# BLDC_Controller_Sch.net
KiCad netlist of a schematic drawn in Altium Designer
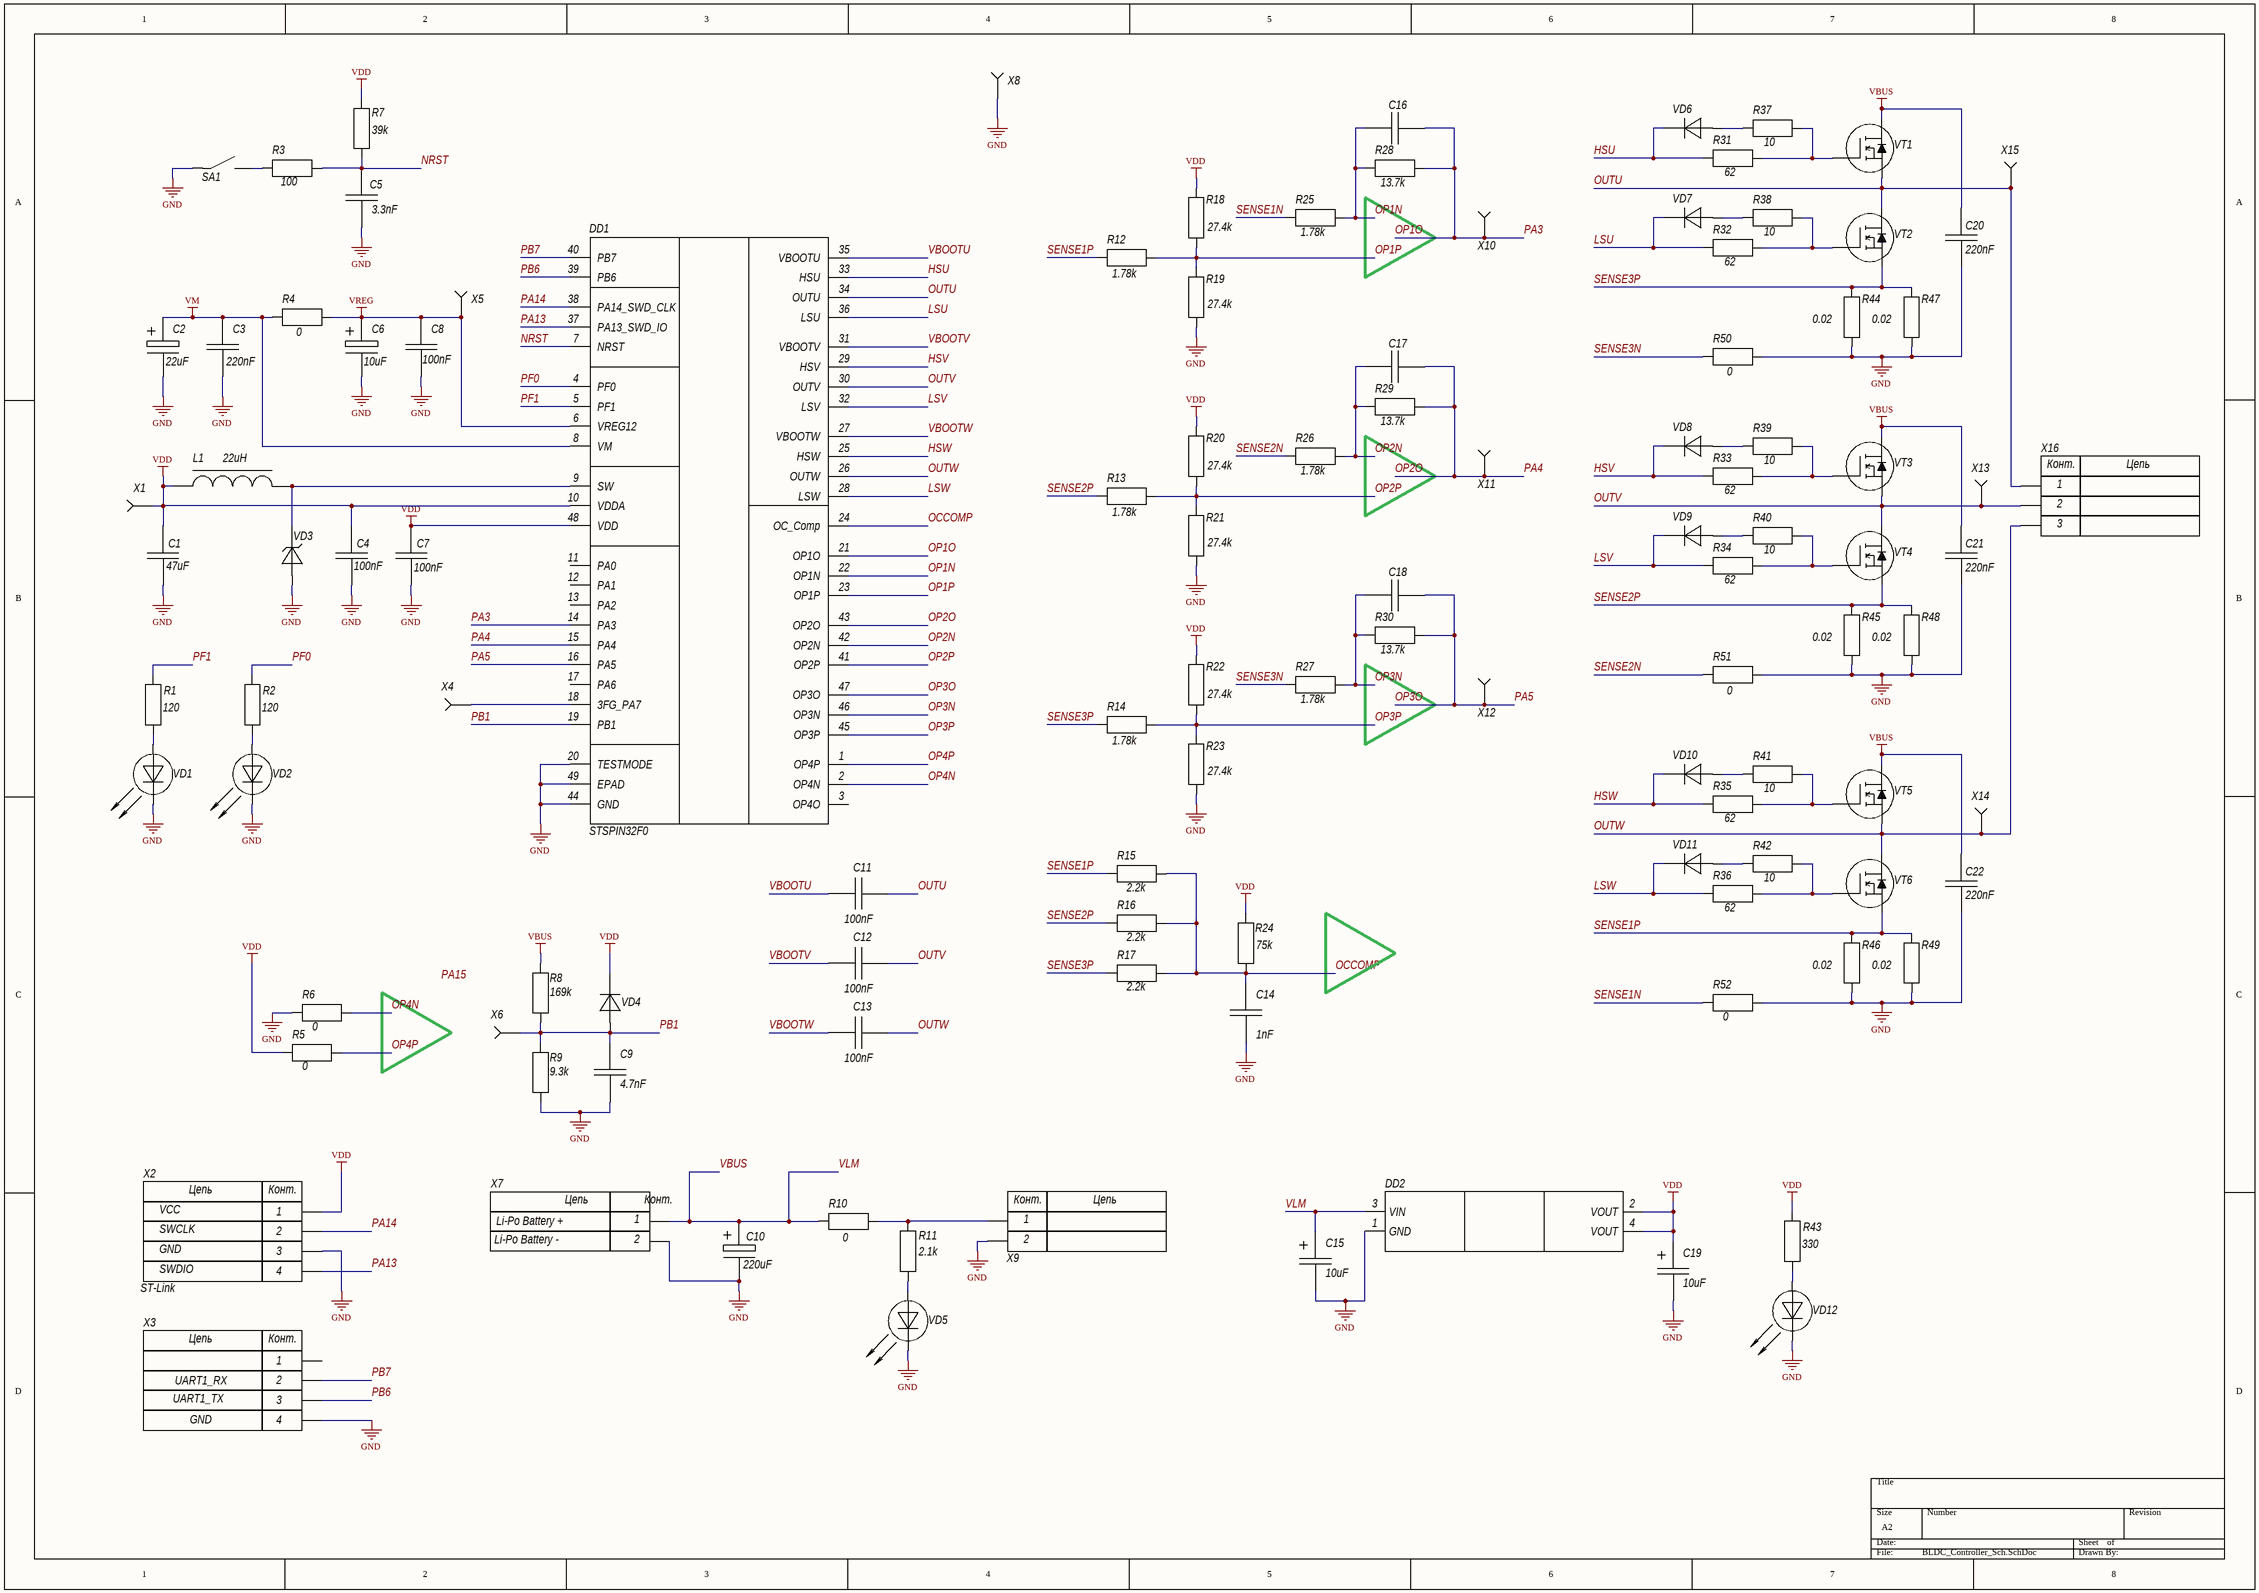
[diagram p0: BLDC_Controller_Sch.SchDoc]

(export (version "E")
  (design (tool "Eeschema 10.0.6"))
  (components
    (comp (ref "C1")
      (value "47uF")
      (footprint "CAP EIA 0603")
      (fields (field (name "Comment") "Cap EIA 0603"))
      (libsource (lib "Capacitors") (part "Cap EIA 0603"))
    )
    (comp (ref "C2")
      (value "22uF")
      (footprint "CAP EL CASE F")
      (description "8.0x10.5 mm Surface Mount Aluminum Electrolytic Capacitor")
      (fields (field (name "Comment") "Cap El SMT Case F"))
      (libsource (lib "Capacitors") (part "Cap El SMT Case F"))
    )
    (comp (ref "C3")
      (value "220nF")
      (footprint "CAP EIA 0805")
      (fields (field (name "Comment") "Cap EIA 0805"))
      (libsource (lib "Capacitors") (part "Cap EIA 0805"))
    )
    (comp (ref "C4")
      (value "100nF")
      (footprint "CAP EIA 0603")
      (fields (field (name "Comment") "Cap EIA 0603"))
      (libsource (lib "Capacitors") (part "Cap EIA 0603"))
    )
    (comp (ref "C5")
      (value "3.3nF")
      (footprint "CAP EIA 0805")
      (fields (field (name "Comment") "Cap EIA 0805"))
      (libsource (lib "Capacitors") (part "Cap EIA 0805"))
    )
    (comp (ref "C6")
      (value "10uF")
      (footprint "CAP EL CASE F")
      (description "8.0x10.5 mm Surface Mount Aluminum Electrolytic Capacitor")
      (fields (field (name "Comment") "Cap El SMT Case F"))
      (libsource (lib "Capacitors") (part "Cap El SMT Case F"))
    )
    (comp (ref "C7")
      (value "100nF")
      (footprint "CAP EIA 0603")
      (fields (field (name "Comment") "Cap EIA 0603"))
      (libsource (lib "Capacitors") (part "Cap EIA 0603"))
    )
    (comp (ref "C8")
      (value "100nF")
      (footprint "CAP EIA 0805")
      (fields (field (name "Comment") "Cap EIA 0805"))
      (libsource (lib "Capacitors") (part "Cap EIA 0805"))
    )
    (comp (ref "C9")
      (value "4.7nF")
      (footprint "CAP EIA 0603")
      (fields (field (name "Comment") "Cap EIA 0603"))
      (libsource (lib "Capacitors") (part "Cap EIA 0603"))
    )
    (comp (ref "C10")
      (value "220uF")
      (footprint "CAP EL CASE F")
      (description "8.0x10.5 mm Surface Mount Aluminum Electrolytic Capacitor")
      (fields (field (name "Comment") "Cap El SMT Case F"))
      (libsource (lib "Capacitors") (part "Cap El SMT Case F"))
    )
    (comp (ref "C11")
      (value "100nF")
      (footprint "CAP EIA 0603")
      (fields (field (name "Comment") "Cap EIA 0603"))
      (libsource (lib "Capacitors") (part "Cap EIA 0603"))
    )
    (comp (ref "C12")
      (value "100nF")
      (footprint "CAP EIA 0603")
      (fields (field (name "Comment") "Cap EIA 0603"))
      (libsource (lib "Capacitors") (part "Cap EIA 0603"))
    )
    (comp (ref "C13")
      (value "100nF")
      (footprint "CAP EIA 0603")
      (fields (field (name "Comment") "Cap EIA 0603"))
      (libsource (lib "Capacitors") (part "Cap EIA 0603"))
    )
    (comp (ref "C14")
      (value "1nF")
      (footprint "CAP EIA 0603")
      (fields (field (name "Comment") "Cap EIA 0603"))
      (libsource (lib "Capacitors") (part "Cap EIA 0603"))
    )
    (comp (ref "C15")
      (value "10uF")
      (footprint "CAP CASE A")
      (fields (field (name "Comment") "Cap El Case A (Tantalum)"))
      (libsource (lib "Capacitors") (part "Cap El Case A (Tantalum)"))
    )
    (comp (ref "C16")
      (value "Cap EIA 0603")
      (footprint "CAP EIA 0603")
      (libsource (lib "Capacitors") (part "Cap EIA 0603"))
    )
    (comp (ref "C17")
      (value "Cap EIA 0603")
      (footprint "CAP EIA 0603")
      (libsource (lib "Capacitors") (part "Cap EIA 0603"))
    )
    (comp (ref "C18")
      (value "Cap EIA 0603")
      (footprint "CAP EIA 0603")
      (libsource (lib "Capacitors") (part "Cap EIA 0603"))
    )
    (comp (ref "C19")
      (value "10uF")
      (footprint "CAP CASE A")
      (fields (field (name "Comment") "Cap El Case A (Tantalum)"))
      (libsource (lib "Capacitors") (part "Cap El Case A (Tantalum)"))
    )
    (comp (ref "C20")
      (value "220nF")
      (footprint "CAP EIA 0805")
      (fields (field (name "Comment") "Cap EIA 0805"))
      (libsource (lib "Capacitors") (part "Cap EIA 0805"))
    )
    (comp (ref "C21")
      (value "220nF")
      (footprint "CAP EIA 0805")
      (fields (field (name "Comment") "Cap EIA 0805"))
      (libsource (lib "Capacitors") (part "Cap EIA 0805"))
    )
    (comp (ref "C22")
      (value "220nF")
      (footprint "CAP EIA 0805")
      (fields (field (name "Comment") "Cap EIA 0805"))
      (libsource (lib "Capacitors") (part "Cap EIA 0805"))
    )
    (comp (ref "DD1")
      (value "STSPIN32F0")
      (footprint "VFQFPN48 7 x 7 x 1.0 - 48L")
      (description "Микросхема управления бесколлекторным эл.двигателем")
      (libsource (lib "Integrated_Circuits") (part "STSPIN32F0"))
    )
    (comp (ref "DD2")
      (value "LM1117S50")
      (footprint "SOT-223_M")
      (description "LDO Voltage Regulator")
      (fields (field (name "MANUFACTURER") "ST Microelectronics"))
      (libsource (lib "Integrated_Circuits") (part "LM1117S50"))
    )
    (comp (ref "L1")
      (value "22uH")
      (footprint "SRN3015")
      (description "Semi-shielded Power Inductors")
      (fields (field (name "MANUFACTURER") "Bourns"))
      (libsource (lib "Inductors") (part "SRN3015"))
    )
    (comp (ref "R1")
      (value "120")
      (footprint "RES EIA 0603")
      (fields (field (name "Comment") "Res EIA 0603"))
      (libsource (lib "Resistors") (part "Res EIA 0603"))
    )
    (comp (ref "R2")
      (value "120")
      (footprint "RES EIA 0603")
      (fields (field (name "Comment") "Res EIA 0603"))
      (libsource (lib "Resistors") (part "Res EIA 0603"))
    )
    (comp (ref "R3")
      (value "100")
      (footprint "RES EIA 0603")
      (fields (field (name "Comment") "Res EIA 0603"))
      (libsource (lib "Resistors") (part "Res EIA 0603"))
    )
    (comp (ref "R4")
      (value "0")
      (footprint "RES EIA 0603")
      (fields (field (name "Comment") "Res EIA 0603"))
      (libsource (lib "Resistors") (part "Res EIA 0603"))
    )
    (comp (ref "R5")
      (value "0")
      (footprint "RES EIA 0603")
      (fields (field (name "Comment") "Res EIA 0603"))
      (libsource (lib "Resistors") (part "Res EIA 0603"))
    )
    (comp (ref "R6")
      (value "0")
      (footprint "RES EIA 0603")
      (fields (field (name "Comment") "Res EIA 0603"))
      (libsource (lib "Resistors") (part "Res EIA 0603"))
    )
    (comp (ref "R7")
      (value "39k")
      (footprint "RES EIA 0603")
      (fields (field (name "Comment") "Res EIA 0603"))
      (libsource (lib "Resistors") (part "Res EIA 0603"))
    )
    (comp (ref "R8")
      (value "169k")
      (footprint "RES EIA 0603")
      (fields (field (name "Comment") "Res EIA 0603"))
      (libsource (lib "Resistors") (part "Res EIA 0603"))
    )
    (comp (ref "R9")
      (value "9.3k")
      (footprint "RES EIA 0603")
      (fields (field (name "Comment") "Res EIA 0603"))
      (libsource (lib "Resistors") (part "Res EIA 0603"))
    )
    (comp (ref "R10")
      (value "0")
      (footprint "RES EIA 0603")
      (fields (field (name "Comment") "Res EIA 0603"))
      (libsource (lib "Resistors") (part "Res EIA 0603"))
    )
    (comp (ref "R11")
      (value "2.1k")
      (footprint "RES EIA 0805")
      (fields (field (name "Comment") "Res EIA 0805"))
      (libsource (lib "Resistors") (part "Res EIA 0805"))
    )
    (comp (ref "R12")
      (value "1.78k")
      (footprint "RES EIA 0603")
      (fields (field (name "Comment") "Res EIA 0603"))
      (libsource (lib "Resistors") (part "Res EIA 0603"))
    )
    (comp (ref "R13")
      (value "1.78k")
      (footprint "RES EIA 0603")
      (fields (field (name "Comment") "Res EIA 0603"))
      (libsource (lib "Resistors") (part "Res EIA 0603"))
    )
    (comp (ref "R14")
      (value "1.78k")
      (footprint "RES EIA 0603")
      (fields (field (name "Comment") "Res EIA 0603"))
      (libsource (lib "Resistors") (part "Res EIA 0603"))
    )
    (comp (ref "R15")
      (value "2.2k")
      (footprint "RES EIA 0603")
      (fields (field (name "Comment") "Res EIA 0603"))
      (libsource (lib "Resistors") (part "Res EIA 0603"))
    )
    (comp (ref "R16")
      (value "2.2k")
      (footprint "RES EIA 0603")
      (fields (field (name "Comment") "Res EIA 0603"))
      (libsource (lib "Resistors") (part "Res EIA 0603"))
    )
    (comp (ref "R17")
      (value "2.2k")
      (footprint "RES EIA 0603")
      (fields (field (name "Comment") "Res EIA 0603"))
      (libsource (lib "Resistors") (part "Res EIA 0603"))
    )
    (comp (ref "R18")
      (value "27.4k")
      (footprint "RES EIA 0603")
      (fields (field (name "Comment") "Res EIA 0603"))
      (libsource (lib "Resistors") (part "Res EIA 0603"))
    )
    (comp (ref "R19")
      (value "27.4k")
      (footprint "RES EIA 0603")
      (fields (field (name "Comment") "Res EIA 0603"))
      (libsource (lib "Resistors") (part "Res EIA 0603"))
    )
    (comp (ref "R20")
      (value "27.4k")
      (footprint "RES EIA 0603")
      (fields (field (name "Comment") "Res EIA 0603"))
      (libsource (lib "Resistors") (part "Res EIA 0603"))
    )
    (comp (ref "R21")
      (value "27.4k")
      (footprint "RES EIA 0603")
      (fields (field (name "Comment") "Res EIA 0603"))
      (libsource (lib "Resistors") (part "Res EIA 0603"))
    )
    (comp (ref "R22")
      (value "27.4k")
      (footprint "RES EIA 0603")
      (fields (field (name "Comment") "Res EIA 0603"))
      (libsource (lib "Resistors") (part "Res EIA 0603"))
    )
    (comp (ref "R23")
      (value "27.4k")
      (footprint "RES EIA 0603")
      (fields (field (name "Comment") "Res EIA 0603"))
      (libsource (lib "Resistors") (part "Res EIA 0603"))
    )
    (comp (ref "R24")
      (value "75k")
      (footprint "RES EIA 0603")
      (fields (field (name "Comment") "Res EIA 0603"))
      (libsource (lib "Resistors") (part "Res EIA 0603"))
    )
    (comp (ref "R25")
      (value "1.78k")
      (footprint "RES EIA 0603")
      (fields (field (name "Comment") "Res EIA 0603"))
      (libsource (lib "Resistors") (part "Res EIA 0603"))
    )
    (comp (ref "R26")
      (value "1.78k")
      (footprint "RES EIA 0603")
      (fields (field (name "Comment") "Res EIA 0603"))
      (libsource (lib "Resistors") (part "Res EIA 0603"))
    )
    (comp (ref "R27")
      (value "1.78k")
      (footprint "RES EIA 0603")
      (fields (field (name "Comment") "Res EIA 0603"))
      (libsource (lib "Resistors") (part "Res EIA 0603"))
    )
    (comp (ref "R28")
      (value "13.7k")
      (footprint "RES EIA 0603")
      (fields (field (name "Comment") "Res EIA 0603"))
      (libsource (lib "Resistors") (part "Res EIA 0603"))
    )
    (comp (ref "R29")
      (value "13.7k")
      (footprint "RES EIA 0603")
      (fields (field (name "Comment") "Res EIA 0603"))
      (libsource (lib "Resistors") (part "Res EIA 0603"))
    )
    (comp (ref "R30")
      (value "13.7k")
      (footprint "RES EIA 0603")
      (fields (field (name "Comment") "Res EIA 0603"))
      (libsource (lib "Resistors") (part "Res EIA 0603"))
    )
    (comp (ref "R31")
      (value "62")
      (footprint "RES EIA 0603")
      (fields (field (name "Comment") "Res EIA 0603"))
      (libsource (lib "Resistors") (part "Res EIA 0603"))
    )
    (comp (ref "R32")
      (value "62")
      (footprint "RES EIA 0603")
      (fields (field (name "Comment") "Res EIA 0603"))
      (libsource (lib "Resistors") (part "Res EIA 0603"))
    )
    (comp (ref "R33")
      (value "62")
      (footprint "RES EIA 0603")
      (fields (field (name "Comment") "Res EIA 0603"))
      (libsource (lib "Resistors") (part "Res EIA 0603"))
    )
    (comp (ref "R34")
      (value "62")
      (footprint "RES EIA 0603")
      (fields (field (name "Comment") "Res EIA 0603"))
      (libsource (lib "Resistors") (part "Res EIA 0603"))
    )
    (comp (ref "R35")
      (value "62")
      (footprint "RES EIA 0603")
      (fields (field (name "Comment") "Res EIA 0603"))
      (libsource (lib "Resistors") (part "Res EIA 0603"))
    )
    (comp (ref "R36")
      (value "62")
      (footprint "RES EIA 0603")
      (fields (field (name "Comment") "Res EIA 0603"))
      (libsource (lib "Resistors") (part "Res EIA 0603"))
    )
    (comp (ref "R37")
      (value "10")
      (footprint "RES EIA 0603")
      (fields (field (name "Comment") "Res EIA 0603"))
      (libsource (lib "Resistors") (part "Res EIA 0603"))
    )
    (comp (ref "R38")
      (value "10")
      (footprint "RES EIA 0603")
      (fields (field (name "Comment") "Res EIA 0603"))
      (libsource (lib "Resistors") (part "Res EIA 0603"))
    )
    (comp (ref "R39")
      (value "10")
      (footprint "RES EIA 0603")
      (fields (field (name "Comment") "Res EIA 0603"))
      (libsource (lib "Resistors") (part "Res EIA 0603"))
    )
    (comp (ref "R40")
      (value "10")
      (footprint "RES EIA 0603")
      (fields (field (name "Comment") "Res EIA 0603"))
      (libsource (lib "Resistors") (part "Res EIA 0603"))
    )
    (comp (ref "R41")
      (value "10")
      (footprint "RES EIA 0603")
      (fields (field (name "Comment") "Res EIA 0603"))
      (libsource (lib "Resistors") (part "Res EIA 0603"))
    )
    (comp (ref "R42")
      (value "10")
      (footprint "RES EIA 0603")
      (fields (field (name "Comment") "Res EIA 0603"))
      (libsource (lib "Resistors") (part "Res EIA 0603"))
    )
    (comp (ref "R43")
      (value "330")
      (footprint "RES EIA 0603")
      (fields (field (name "Comment") "Res EIA 0603"))
      (libsource (lib "Resistors") (part "Res EIA 0603"))
    )
    (comp (ref "R44")
      (value "0.02")
      (footprint "RES EIA 2512")
      (fields (field (name "Comment") "Res EIA 2512"))
      (libsource (lib "Resistors") (part "Res EIA 2512"))
    )
    (comp (ref "R45")
      (value "0.02")
      (footprint "RES EIA 2512")
      (fields (field (name "Comment") "Res EIA 2512"))
      (libsource (lib "Resistors") (part "Res EIA 2512"))
    )
    (comp (ref "R46")
      (value "0.02")
      (footprint "RES EIA 2512")
      (fields (field (name "Comment") "Res EIA 2512"))
      (libsource (lib "Resistors") (part "Res EIA 2512"))
    )
    (comp (ref "R47")
      (value "0.02")
      (footprint "RES EIA 2512")
      (fields (field (name "Comment") "Res EIA 2512"))
      (libsource (lib "Resistors") (part "Res EIA 2512"))
    )
    (comp (ref "R48")
      (value "0.02")
      (footprint "RES EIA 2512")
      (fields (field (name "Comment") "Res EIA 2512"))
      (libsource (lib "Resistors") (part "Res EIA 2512"))
    )
    (comp (ref "R49")
      (value "0.02")
      (footprint "RES EIA 2512")
      (fields (field (name "Comment") "Res EIA 2512"))
      (libsource (lib "Resistors") (part "Res EIA 2512"))
    )
    (comp (ref "R50")
      (value "0")
      (footprint "RES EIA 0603")
      (fields (field (name "Comment") "Res EIA 0603"))
      (libsource (lib "Resistors") (part "Res EIA 0603"))
    )
    (comp (ref "R51")
      (value "0")
      (footprint "RES EIA 0603")
      (fields (field (name "Comment") "Res EIA 0603"))
      (libsource (lib "Resistors") (part "Res EIA 0603"))
    )
    (comp (ref "R52")
      (value "0")
      (footprint "RES EIA 0603")
      (fields (field (name "Comment") "Res EIA 0603"))
      (libsource (lib "Resistors") (part "Res EIA 0603"))
    )
    (comp (ref "SA1")
      (value "IT-1187")
      (footprint "IT-1187")
      (description "Тактовая кнопка")
      (fields (field (name "MANUFACTURER") "Switronic Industrial Corp."))
      (libsource (lib "Switching_Devices") (part "IT-1187"))
    )
    (comp (ref "VD1")
      (value "KP-2012xxxx")
      (footprint "SMD LED 0805 (GREEN)")
      (description "SMD Led")
      (libsource (lib "Semiconductors") (part "FYLS-0805xxxx"))
    )
    (comp (ref "VD2")
      (value "KP-2012xxxx")
      (footprint "SMD LED 0805 (GREEN)")
      (description "SMD Led")
      (libsource (lib "Semiconductors") (part "FYLS-0805xxxx"))
    )
    (comp (ref "VD3")
      (value "SMCJ5.0A")
      (footprint "DO-214AB")
      (description "TVS Диод, двунаправленный, Uраб. = 5В, Uпроб. = 6,74В, P = 1500 Вт")
      (libsource (lib "Semiconductors") (part "SMCJ5.0A"))
    )
    (comp (ref "VD4")
      (value "BAT54HT1G")
      (footprint "SOD-323")
      (description "SCHOTTKY BARRIER DIOD 0.2 AMPERES, 30 VOLTS")
      (libsource (lib "Semiconductors") (part "BAT54HT1G"))
    )
    (comp (ref "VD5")
      (value "KP-2012xxxx")
      (footprint "SMD LED 0805 (GREEN)")
      (description "SMD Led")
      (libsource (lib "Semiconductors") (part "FYLS-0805xxxx"))
    )
    (comp (ref "VD6")
      (value "4148WS")
      (footprint "SOD-323")
      (description "Diod, 150mA, 100V(SOD-323)")
      (libsource (lib "Semiconductors") (part "4148WS"))
    )
    (comp (ref "VD7")
      (value "4148WS")
      (footprint "SOD-323")
      (description "Diod, 150mA, 100V(SOD-323)")
      (libsource (lib "Semiconductors") (part "4148WS"))
    )
    (comp (ref "VD8")
      (value "4148WS")
      (footprint "SOD-323")
      (description "Diod, 150mA, 100V(SOD-323)")
      (libsource (lib "Semiconductors") (part "4148WS"))
    )
    (comp (ref "VD9")
      (value "4148WS")
      (footprint "SOD-323")
      (description "Diod, 150mA, 100V(SOD-323)")
      (libsource (lib "Semiconductors") (part "4148WS"))
    )
    (comp (ref "VD10")
      (value "4148WS")
      (footprint "SOD-323")
      (description "Diod, 150mA, 100V(SOD-323)")
      (libsource (lib "Semiconductors") (part "4148WS"))
    )
    (comp (ref "VD11")
      (value "4148WS")
      (footprint "SOD-323")
      (description "Diod, 150mA, 100V(SOD-323)")
      (libsource (lib "Semiconductors") (part "4148WS"))
    )
    (comp (ref "VD12")
      (value "KP-2012xxxx")
      (footprint "SMD LED 0805 (GREEN)")
      (description "SMD Led")
      (libsource (lib "Semiconductors") (part "FYLS-0805xxxx"))
    )
    (comp (ref "VT1")
      (value "IRLZ44NS")
      (footprint "D2PAK_M")
      (description "HEXFET Power MOSFET")
      (fields (field (name "MANUFACTURER") "International Rectifier"))
      (libsource (lib "Semiconductors") (part "IRLZ44NS"))
    )
    (comp (ref "VT2")
      (value "IRLZ44NS")
      (footprint "D2PAK_M")
      (description "HEXFET Power MOSFET")
      (fields (field (name "MANUFACTURER") "International Rectifier"))
      (libsource (lib "Semiconductors") (part "IRLZ44NS"))
    )
    (comp (ref "VT3")
      (value "IRLZ44NS")
      (footprint "D2PAK_M")
      (description "HEXFET Power MOSFET")
      (fields (field (name "MANUFACTURER") "International Rectifier"))
      (libsource (lib "Semiconductors") (part "IRLZ44NS"))
    )
    (comp (ref "VT4")
      (value "IRLZ44NS")
      (footprint "D2PAK_M")
      (description "HEXFET Power MOSFET")
      (fields (field (name "MANUFACTURER") "International Rectifier"))
      (libsource (lib "Semiconductors") (part "IRLZ44NS"))
    )
    (comp (ref "VT5")
      (value "IRLZ44NS")
      (footprint "D2PAK_M")
      (description "HEXFET Power MOSFET")
      (fields (field (name "MANUFACTURER") "International Rectifier"))
      (libsource (lib "Semiconductors") (part "IRLZ44NS"))
    )
    (comp (ref "VT6")
      (value "IRLZ44NS")
      (footprint "D2PAK_M")
      (description "HEXFET Power MOSFET")
      (fields (field (name "MANUFACTURER") "International Rectifier"))
      (libsource (lib "Semiconductors") (part "IRLZ44NS"))
    )
    (comp (ref "X1")
      (value "Pin")
      (footprint "Pin")
      (description "Generic Pin Contact")
      (libsource (lib "Connectors") (part "Pin"))
    )
    (comp (ref "X2")
      (value "ST-Link")
      (footprint "SWD")
      (fields (field (name "MANUFACTURER") "Тайвань(Китай)"))
      (libsource (lib "Connectors") (part "SWD(PLS- 4)"))
    )
    (comp (ref "X3")
      (value "PLS-4")
      (footprint "SWD")
      (fields (field (name "MANUFACTURER") "Hsuan Mao(Китай)"))
      (libsource (lib "Connectors") (part "PLS-4"))
    )
    (comp (ref "X4")
      (value "Pin")
      (footprint "Pin")
      (description "Generic Pin Contact")
      (libsource (lib "Connectors") (part "Pin"))
    )
    (comp (ref "X5")
      (value "Pin")
      (footprint "Pin")
      (description "Generic Pin Contact")
      (libsource (lib "Connectors") (part "Pin"))
    )
    (comp (ref "X6")
      (value "Pin")
      (footprint "Pin")
      (description "Generic Pin Contact")
      (libsource (lib "Connectors") (part "Pin"))
    )
    (comp (ref "X7") (value "TB2") (footprint "TB2") (libsource (lib "Connectors") (part "TB2")))
    (comp (ref "X8")
      (value "Pin")
      (footprint "Pin")
      (description "Generic Pin Contact")
      (libsource (lib "Connectors") (part "Pin"))
    )
    (comp (ref "X9") (value "TB2") (footprint "TB2") (libsource (lib "Connectors") (part "TB2")))
    (comp (ref "X10")
      (value "Pin")
      (footprint "Pin")
      (description "Generic Pin Contact")
      (libsource (lib "Connectors") (part "Pin"))
    )
    (comp (ref "X11")
      (value "Pin")
      (footprint "Pin")
      (description "Generic Pin Contact")
      (libsource (lib "Connectors") (part "Pin"))
    )
    (comp (ref "X12")
      (value "Pin")
      (footprint "Pin")
      (description "Generic Pin Contact")
      (libsource (lib "Connectors") (part "Pin"))
    )
    (comp (ref "X13")
      (value "Pin")
      (footprint "Pin")
      (description "Generic Pin Contact")
      (libsource (lib "Connectors") (part "Pin"))
    )
    (comp (ref "X14")
      (value "Pin")
      (footprint "Pin")
      (description "Generic Pin Contact")
      (libsource (lib "Connectors") (part "Pin"))
    )
    (comp (ref "X15")
      (value "Pin")
      (footprint "Pin")
      (description "Generic Pin Contact")
      (libsource (lib "Connectors") (part "Pin"))
    )
    (comp (ref "X16") (value "TB3") (footprint "TB3") (libsource (lib "Connectors") (part "TB3")))
  )
  (nets
    (net (code "1") (name "/HSU") (class "Default")
      (node (ref "DD1") (pin "33") (pinfunction "HSU_33") (pintype "passive"))
      (node (ref "R31") (pin "1") (pinfunction "1_1") (pintype "passive"))
      (node (ref "VD6") (pin "1") (pinfunction "K_1") (pintype "passive"))
    )
    (net (code "2") (name "/HSV") (class "Default")
      (node (ref "DD1") (pin "29") (pinfunction "HSV_29") (pintype "passive"))
      (node (ref "R33") (pin "1") (pinfunction "1_1") (pintype "passive"))
      (node (ref "VD8") (pin "1") (pinfunction "K_1") (pintype "passive"))
    )
    (net (code "3") (name "/HSW") (class "Default")
      (node (ref "DD1") (pin "25") (pinfunction "HSW_25") (pintype "passive"))
      (node (ref "R35") (pin "1") (pinfunction "1_1") (pintype "passive"))
      (node (ref "VD10") (pin "1") (pinfunction "K_1") (pintype "passive"))
    )
    (net (code "4") (name "/LSU") (class "Default")
      (node (ref "DD1") (pin "36") (pinfunction "LSU_36") (pintype "passive"))
      (node (ref "R32") (pin "1") (pinfunction "1_1") (pintype "passive"))
      (node (ref "VD7") (pin "1") (pinfunction "K_1") (pintype "passive"))
    )
    (net (code "5") (name "/LSV") (class "Default")
      (node (ref "DD1") (pin "32") (pinfunction "LSV_32") (pintype "passive"))
      (node (ref "R34") (pin "1") (pinfunction "1_1") (pintype "passive"))
      (node (ref "VD9") (pin "1") (pinfunction "K_1") (pintype "passive"))
    )
    (net (code "6") (name "/LSW") (class "Default")
      (node (ref "DD1") (pin "28") (pinfunction "LSW_28") (pintype "passive"))
      (node (ref "R36") (pin "1") (pinfunction "1_1") (pintype "passive"))
      (node (ref "VD11") (pin "1") (pinfunction "K_1") (pintype "passive"))
    )
    (net (code "7") (name "/NRST") (class "Default")
      (node (ref "C5") (pin "2") (pinfunction "2_2") (pintype "passive"))
      (node (ref "DD1") (pin "7") (pinfunction "NRST_7") (pintype "passive"))
      (node (ref "R3") (pin "2") (pinfunction "2_2") (pintype "passive"))
      (node (ref "R7") (pin "1") (pinfunction "1_1") (pintype "passive"))
    )
    (net (code "8") (name "/OCCOMP") (class "Default")
      (node (ref "C14") (pin "2") (pinfunction "2_2") (pintype "passive"))
      (node (ref "DD1") (pin "24") (pinfunction "OC_Comp_24") (pintype "passive"))
      (node (ref "R15") (pin "2") (pinfunction "2_2") (pintype "passive"))
      (node (ref "R16") (pin "2") (pinfunction "2_2") (pintype "passive"))
      (node (ref "R17") (pin "2") (pinfunction "2_2") (pintype "passive"))
      (node (ref "R24") (pin "1") (pinfunction "1_1") (pintype "passive"))
    )
    (net (code "9") (name "/OP1N") (class "Default")
      (node (ref "C16") (pin "1") (pinfunction "1_1") (pintype "passive"))
      (node (ref "DD1") (pin "22") (pinfunction "OP1N_22") (pintype "passive"))
      (node (ref "R25") (pin "2") (pinfunction "2_2") (pintype "passive"))
      (node (ref "R28") (pin "1") (pinfunction "1_1") (pintype "passive"))
    )
    (net (code "10") (name "/OP1O") (class "Default")
      (node (ref "C16") (pin "2") (pinfunction "2_2") (pintype "passive"))
      (node (ref "DD1") (pin "14") (pinfunction "PA3_14") (pintype "passive"))
      (node (ref "DD1") (pin "21") (pinfunction "OP1O_21") (pintype "passive"))
      (node (ref "R28") (pin "2") (pinfunction "2_2") (pintype "passive"))
      (node (ref "X10") (pin "1") (pinfunction "1_1") (pintype "passive"))
    )
    (net (code "11") (name "/OP1P") (class "Default")
      (node (ref "DD1") (pin "23") (pinfunction "OP1P_23") (pintype "passive"))
      (node (ref "R12") (pin "2") (pinfunction "2_2") (pintype "passive"))
      (node (ref "R18") (pin "1") (pinfunction "1_1") (pintype "passive"))
      (node (ref "R19") (pin "2") (pinfunction "2_2") (pintype "passive"))
    )
    (net (code "12") (name "/OP2N") (class "Default")
      (node (ref "C17") (pin "1") (pinfunction "1_1") (pintype "passive"))
      (node (ref "DD1") (pin "42") (pinfunction "OP2N_42") (pintype "passive"))
      (node (ref "R26") (pin "2") (pinfunction "2_2") (pintype "passive"))
      (node (ref "R29") (pin "1") (pinfunction "1_1") (pintype "passive"))
    )
    (net (code "13") (name "/OP2O") (class "Default")
      (node (ref "C17") (pin "2") (pinfunction "2_2") (pintype "passive"))
      (node (ref "DD1") (pin "15") (pinfunction "PA4_15") (pintype "passive"))
      (node (ref "DD1") (pin "43") (pinfunction "OP2O_43") (pintype "passive"))
      (node (ref "R29") (pin "2") (pinfunction "2_2") (pintype "passive"))
      (node (ref "X11") (pin "1") (pinfunction "1_1") (pintype "passive"))
    )
    (net (code "14") (name "/OP2P") (class "Default")
      (node (ref "DD1") (pin "41") (pinfunction "OP2P_41") (pintype "passive"))
      (node (ref "R13") (pin "2") (pinfunction "2_2") (pintype "passive"))
      (node (ref "R20") (pin "1") (pinfunction "1_1") (pintype "passive"))
      (node (ref "R21") (pin "2") (pinfunction "2_2") (pintype "passive"))
    )
    (net (code "15") (name "/OP3N") (class "Default")
      (node (ref "C18") (pin "1") (pinfunction "1_1") (pintype "passive"))
      (node (ref "DD1") (pin "46") (pinfunction "OP3N_46") (pintype "passive"))
      (node (ref "R27") (pin "2") (pinfunction "2_2") (pintype "passive"))
      (node (ref "R30") (pin "1") (pinfunction "1_1") (pintype "passive"))
    )
    (net (code "16") (name "/OP3O") (class "Default")
      (node (ref "C18") (pin "2") (pinfunction "2_2") (pintype "passive"))
      (node (ref "DD1") (pin "16") (pinfunction "PA5_16") (pintype "passive"))
      (node (ref "DD1") (pin "47") (pinfunction "OP3O_47") (pintype "passive"))
      (node (ref "R30") (pin "2") (pinfunction "2_2") (pintype "passive"))
      (node (ref "X12") (pin "1") (pinfunction "1_1") (pintype "passive"))
    )
    (net (code "17") (name "/OP3P") (class "Default")
      (node (ref "DD1") (pin "45") (pinfunction "OP3P_45") (pintype "passive"))
      (node (ref "R14") (pin "2") (pinfunction "2_2") (pintype "passive"))
      (node (ref "R22") (pin "1") (pinfunction "1_1") (pintype "passive"))
      (node (ref "R23") (pin "2") (pinfunction "2_2") (pintype "passive"))
    )
    (net (code "18") (name "/OP4N") (class "Default")
      (node (ref "DD1") (pin "2") (pinfunction "OP4N_2") (pintype "passive"))
      (node (ref "R6") (pin "2") (pinfunction "2_2") (pintype "passive"))
    )
    (net (code "19") (name "/OP4P") (class "Default")
      (node (ref "DD1") (pin "1") (pinfunction "OP4P_1") (pintype "passive"))
      (node (ref "R5") (pin "2") (pinfunction "2_2") (pintype "passive"))
    )
    (net (code "20") (name "/OUTU") (class "Default")
      (node (ref "C11") (pin "2") (pinfunction "2_2") (pintype "passive"))
      (node (ref "DD1") (pin "34") (pinfunction "OUTU_34") (pintype "passive"))
      (node (ref "VT1") (pin "3") (pinfunction "S_3") (pintype "passive"))
      (node (ref "VT2") (pin "2") (pinfunction "D_2") (pintype "passive"))
      (node (ref "X15") (pin "1") (pinfunction "1_1") (pintype "passive"))
      (node (ref "X16") (pin "1") (pinfunction "1_1") (pintype "passive"))
    )
    (net (code "21") (name "/OUTV") (class "Default")
      (node (ref "C12") (pin "2") (pinfunction "2_2") (pintype "passive"))
      (node (ref "DD1") (pin "30") (pinfunction "OUTV_30") (pintype "passive"))
      (node (ref "VT3") (pin "3") (pinfunction "S_3") (pintype "passive"))
      (node (ref "VT4") (pin "2") (pinfunction "D_2") (pintype "passive"))
      (node (ref "X13") (pin "1") (pinfunction "1_1") (pintype "passive"))
      (node (ref "X16") (pin "2") (pinfunction "2_2") (pintype "passive"))
    )
    (net (code "22") (name "/OUTW") (class "Default")
      (node (ref "C13") (pin "2") (pinfunction "2_2") (pintype "passive"))
      (node (ref "DD1") (pin "26") (pinfunction "OUTW_26") (pintype "passive"))
      (node (ref "VT5") (pin "3") (pinfunction "S_3") (pintype "passive"))
      (node (ref "VT6") (pin "2") (pinfunction "D_2") (pintype "passive"))
      (node (ref "X14") (pin "1") (pinfunction "1_1") (pintype "passive"))
      (node (ref "X16") (pin "3") (pinfunction "3_3") (pintype "passive"))
    )
    (net (code "23") (name "/PA13") (class "Default")
      (node (ref "DD1") (pin "37") (pinfunction "PA13_SWD_IO_37") (pintype "passive"))
      (node (ref "X2") (pin "4") (pinfunction "SWDIO_4") (pintype "passive"))
    )
    (net (code "24") (name "/PA14") (class "Default")
      (node (ref "DD1") (pin "38") (pinfunction "PA14_SWD_CLK_38") (pintype "passive"))
      (node (ref "X2") (pin "2") (pinfunction "SWCLK_2") (pintype "passive"))
    )
    (net (code "26") (name "/PB1") (class "Default")
      (node (ref "C9") (pin "2") (pinfunction "2_2") (pintype "passive"))
      (node (ref "DD1") (pin "19") (pinfunction "PB1_19") (pintype "passive"))
      (node (ref "R8") (pin "1") (pinfunction "1_1") (pintype "passive"))
      (node (ref "R9") (pin "2") (pinfunction "2_2") (pintype "passive"))
      (node (ref "VD4") (pin "1") (pinfunction "A_1") (pintype "passive"))
      (node (ref "X6") (pin "1") (pinfunction "1_1") (pintype "passive"))
    )
    (net (code "27") (name "/PB6") (class "Default")
      (node (ref "DD1") (pin "39") (pinfunction "PB6_39") (pintype "passive"))
      (node (ref "X3") (pin "3") (pinfunction "3_3") (pintype "passive"))
    )
    (net (code "28") (name "/PB7") (class "Default")
      (node (ref "DD1") (pin "40") (pinfunction "PB7_40") (pintype "passive"))
      (node (ref "X3") (pin "2") (pinfunction "2_2") (pintype "passive"))
    )
    (net (code "29") (name "/PF0") (class "Default")
      (node (ref "DD1") (pin "4") (pinfunction "PF0_4") (pintype "passive"))
      (node (ref "R2") (pin "1") (pinfunction "1_1") (pintype "passive"))
    )
    (net (code "30") (name "/PF1") (class "Default")
      (node (ref "DD1") (pin "5") (pinfunction "PF1_5") (pintype "passive"))
      (node (ref "R1") (pin "1") (pinfunction "1_1") (pintype "passive"))
    )
    (net (code "31") (name "/SENSE1N") (class "Default")
      (node (ref "R25") (pin "1") (pinfunction "1_1") (pintype "passive"))
      (node (ref "R52") (pin "1") (pinfunction "1_1") (pintype "passive"))
    )
    (net (code "32") (name "/SENSE1P") (class "Default")
      (node (ref "R12") (pin "1") (pinfunction "1_1") (pintype "passive"))
      (node (ref "R15") (pin "1") (pinfunction "1_1") (pintype "passive"))
      (node (ref "R46") (pin "2") (pinfunction "2_2") (pintype "passive"))
      (node (ref "R49") (pin "1") (pinfunction "1_1") (pintype "passive"))
      (node (ref "VT6") (pin "3") (pinfunction "S_3") (pintype "passive"))
    )
    (net (code "33") (name "/SENSE2N") (class "Default")
      (node (ref "R26") (pin "1") (pinfunction "1_1") (pintype "passive"))
      (node (ref "R51") (pin "1") (pinfunction "1_1") (pintype "passive"))
    )
    (net (code "34") (name "/SENSE2P") (class "Default")
      (node (ref "R13") (pin "1") (pinfunction "1_1") (pintype "passive"))
      (node (ref "R16") (pin "1") (pinfunction "1_1") (pintype "passive"))
      (node (ref "R45") (pin "2") (pinfunction "2_2") (pintype "passive"))
      (node (ref "R48") (pin "1") (pinfunction "1_1") (pintype "passive"))
      (node (ref "VT4") (pin "3") (pinfunction "S_3") (pintype "passive"))
    )
    (net (code "35") (name "/SENSE3N") (class "Default")
      (node (ref "R27") (pin "1") (pinfunction "1_1") (pintype "passive"))
      (node (ref "R50") (pin "1") (pinfunction "1_1") (pintype "passive"))
    )
    (net (code "36") (name "/SENSE3P") (class "Default")
      (node (ref "R14") (pin "1") (pinfunction "1_1") (pintype "passive"))
      (node (ref "R17") (pin "1") (pinfunction "1_1") (pintype "passive"))
      (node (ref "R44") (pin "2") (pinfunction "2_2") (pintype "passive"))
      (node (ref "R47") (pin "1") (pinfunction "1_1") (pintype "passive"))
      (node (ref "VT2") (pin "3") (pinfunction "S_3") (pintype "passive"))
    )
    (net (code "37") (name "/VBOOTU") (class "Default")
      (node (ref "C11") (pin "1") (pinfunction "1_1") (pintype "passive"))
      (node (ref "DD1") (pin "35") (pinfunction "VBOOTU_35") (pintype "passive"))
    )
    (net (code "38") (name "/VBOOTV") (class "Default")
      (node (ref "C12") (pin "1") (pinfunction "1_1") (pintype "passive"))
      (node (ref "DD1") (pin "31") (pinfunction "VBOOTV_31") (pintype "passive"))
    )
    (net (code "39") (name "/VBOOTW") (class "Default")
      (node (ref "C13") (pin "1") (pinfunction "1_1") (pintype "passive"))
      (node (ref "DD1") (pin "27") (pinfunction "VBOOTW_27") (pintype "passive"))
    )
    (net (code "40") (name "GND") (class "Default")
      (node (ref "C1") (pin "1") (pinfunction "1_1") (pintype "passive"))
      (node (ref "C10") (pin "2") (pinfunction "2_2") (pintype "passive"))
      (node (ref "C14") (pin "1") (pinfunction "1_1") (pintype "passive"))
      (node (ref "C15") (pin "2") (pinfunction "2_2") (pintype "passive"))
      (node (ref "C19") (pin "2") (pinfunction "2_2") (pintype "passive"))
      (node (ref "C2") (pin "2") (pinfunction "2_2") (pintype "passive"))
      (node (ref "C20") (pin "1") (pinfunction "1_1") (pintype "passive"))
      (node (ref "C21") (pin "1") (pinfunction "1_1") (pintype "passive"))
      (node (ref "C22") (pin "1") (pinfunction "1_1") (pintype "passive"))
      (node (ref "C3") (pin "1") (pinfunction "1_1") (pintype "passive"))
      (node (ref "C4") (pin "1") (pinfunction "1_1") (pintype "passive"))
      (node (ref "C5") (pin "1") (pinfunction "1_1") (pintype "passive"))
      (node (ref "C6") (pin "2") (pinfunction "2_2") (pintype "passive"))
      (node (ref "C7") (pin "1") (pinfunction "1_1") (pintype "passive"))
      (node (ref "C8") (pin "2") (pinfunction "2_2") (pintype "passive"))
      (node (ref "C9") (pin "1") (pinfunction "1_1") (pintype "passive"))
      (node (ref "DD1") (pin "20") (pinfunction "TESTMODE_20") (pintype "passive"))
      (node (ref "DD1") (pin "44") (pinfunction "GND_44") (pintype "passive"))
      (node (ref "DD1") (pin "49") (pinfunction "EPAD_49") (pintype "passive"))
      (node (ref "DD2") (pin "1") (pinfunction "GND_1") (pintype "passive"))
      (node (ref "R19") (pin "1") (pinfunction "1_1") (pintype "passive"))
      (node (ref "R21") (pin "1") (pinfunction "1_1") (pintype "passive"))
      (node (ref "R23") (pin "1") (pinfunction "1_1") (pintype "passive"))
      (node (ref "R44") (pin "1") (pinfunction "1_1") (pintype "passive"))
      (node (ref "R45") (pin "1") (pinfunction "1_1") (pintype "passive"))
      (node (ref "R46") (pin "1") (pinfunction "1_1") (pintype "passive"))
      (node (ref "R47") (pin "2") (pinfunction "2_2") (pintype "passive"))
      (node (ref "R48") (pin "2") (pinfunction "2_2") (pintype "passive"))
      (node (ref "R49") (pin "2") (pinfunction "2_2") (pintype "passive"))
      (node (ref "R50") (pin "2") (pinfunction "2_2") (pintype "passive"))
      (node (ref "R51") (pin "2") (pinfunction "2_2") (pintype "passive"))
      (node (ref "R52") (pin "2") (pinfunction "2_2") (pintype "passive"))
      (node (ref "R6") (pin "1") (pinfunction "1_1") (pintype "passive"))
      (node (ref "R9") (pin "1") (pinfunction "1_1") (pintype "passive"))
      (node (ref "SA1") (pin "1") (pinfunction "1_1") (pintype "passive"))
      (node (ref "VD1") (pin "2") (pinfunction "K_2") (pintype "passive"))
      (node (ref "VD12") (pin "2") (pinfunction "K_2") (pintype "passive"))
      (node (ref "VD2") (pin "2") (pinfunction "K_2") (pintype "passive"))
      (node (ref "VD3") (pin "2") (pinfunction "A_2") (pintype "passive"))
      (node (ref "VD5") (pin "2") (pinfunction "K_2") (pintype "passive"))
      (node (ref "X2") (pin "3") (pinfunction "GND_3") (pintype "passive"))
      (node (ref "X3") (pin "4") (pinfunction "4_4") (pintype "passive"))
      (node (ref "X7") (pin "2") (pinfunction "2_2") (pintype "passive"))
      (node (ref "X8") (pin "1") (pinfunction "1_1") (pintype "passive"))
      (node (ref "X9") (pin "2") (pinfunction "2_2") (pintype "passive"))
    )
    (net (code "41") (name "Net-(DD1-3FG_PA7)") (class "Default")
      (node (ref "DD1") (pin "18") (pinfunction "3FG_PA7_18") (pintype "passive"))
      (node (ref "X4") (pin "1") (pinfunction "1_1") (pintype "passive"))
    )
    (net (code "42") (name "Net-(DD1-SW)") (class "Default")
      (node (ref "DD1") (pin "9") (pinfunction "SW_9") (pintype "passive"))
      (node (ref "L1") (pin "2") (pinfunction "2_2") (pintype "passive"))
      (node (ref "VD3") (pin "1") (pinfunction "K_1") (pintype "passive"))
    )
    (net (code "43") (name "Net-(R3-Pad1)") (class "Default")
      (node (ref "R3") (pin "1") (pinfunction "1_1") (pintype "passive"))
      (node (ref "SA1") (pin "2") (pinfunction "2_2") (pintype "passive"))
    )
    (net (code "44") (name "Net-(R10-Pad2)") (class "Default")
      (node (ref "R10") (pin "2") (pinfunction "2_2") (pintype "passive"))
      (node (ref "R11") (pin "2") (pinfunction "2_2") (pintype "passive"))
      (node (ref "X9") (pin "1") (pinfunction "1_1") (pintype "passive"))
    )
    (net (code "45") (name "Net-(VD1-A)") (class "Default")
      (node (ref "R1") (pin "2") (pinfunction "2_2") (pintype "passive"))
      (node (ref "VD1") (pin "1") (pinfunction "A_1") (pintype "passive"))
    )
    (net (code "46") (name "Net-(VD2-A)") (class "Default")
      (node (ref "R2") (pin "2") (pinfunction "2_2") (pintype "passive"))
      (node (ref "VD2") (pin "1") (pinfunction "A_1") (pintype "passive"))
    )
    (net (code "47") (name "Net-(VD5-A)") (class "Default")
      (node (ref "R11") (pin "1") (pinfunction "1_1") (pintype "passive"))
      (node (ref "VD5") (pin "1") (pinfunction "A_1") (pintype "passive"))
    )
    (net (code "48") (name "Net-(VD6-A)") (class "Default")
      (node (ref "R37") (pin "1") (pinfunction "1_1") (pintype "passive"))
      (node (ref "VD6") (pin "2") (pinfunction "A_2") (pintype "passive"))
    )
    (net (code "49") (name "Net-(VD7-A)") (class "Default")
      (node (ref "R38") (pin "1") (pinfunction "1_1") (pintype "passive"))
      (node (ref "VD7") (pin "2") (pinfunction "A_2") (pintype "passive"))
    )
    (net (code "50") (name "Net-(VD8-A)") (class "Default")
      (node (ref "R39") (pin "1") (pinfunction "1_1") (pintype "passive"))
      (node (ref "VD8") (pin "2") (pinfunction "A_2") (pintype "passive"))
    )
    (net (code "51") (name "Net-(VD9-A)") (class "Default")
      (node (ref "R40") (pin "1") (pinfunction "1_1") (pintype "passive"))
      (node (ref "VD9") (pin "2") (pinfunction "A_2") (pintype "passive"))
    )
    (net (code "52") (name "Net-(VD10-A)") (class "Default")
      (node (ref "R41") (pin "1") (pinfunction "1_1") (pintype "passive"))
      (node (ref "VD10") (pin "2") (pinfunction "A_2") (pintype "passive"))
    )
    (net (code "53") (name "Net-(VD11-A)") (class "Default")
      (node (ref "R42") (pin "1") (pinfunction "1_1") (pintype "passive"))
      (node (ref "VD11") (pin "2") (pinfunction "A_2") (pintype "passive"))
    )
    (net (code "54") (name "Net-(VD12-A)") (class "Default")
      (node (ref "R43") (pin "2") (pinfunction "2_2") (pintype "passive"))
      (node (ref "VD12") (pin "1") (pinfunction "A_1") (pintype "passive"))
    )
    (net (code "55") (name "Net-(VT1-G)") (class "Default")
      (node (ref "R31") (pin "2") (pinfunction "2_2") (pintype "passive"))
      (node (ref "R37") (pin "2") (pinfunction "2_2") (pintype "passive"))
      (node (ref "VT1") (pin "1") (pinfunction "G_1") (pintype "passive"))
    )
    (net (code "56") (name "Net-(VT2-G)") (class "Default")
      (node (ref "R32") (pin "2") (pinfunction "2_2") (pintype "passive"))
      (node (ref "R38") (pin "2") (pinfunction "2_2") (pintype "passive"))
      (node (ref "VT2") (pin "1") (pinfunction "G_1") (pintype "passive"))
    )
    (net (code "57") (name "Net-(VT3-G)") (class "Default")
      (node (ref "R33") (pin "2") (pinfunction "2_2") (pintype "passive"))
      (node (ref "R39") (pin "2") (pinfunction "2_2") (pintype "passive"))
      (node (ref "VT3") (pin "1") (pinfunction "G_1") (pintype "passive"))
    )
    (net (code "58") (name "Net-(VT4-G)") (class "Default")
      (node (ref "R34") (pin "2") (pinfunction "2_2") (pintype "passive"))
      (node (ref "R40") (pin "2") (pinfunction "2_2") (pintype "passive"))
      (node (ref "VT4") (pin "1") (pinfunction "G_1") (pintype "passive"))
    )
    (net (code "59") (name "Net-(VT5-G)") (class "Default")
      (node (ref "R35") (pin "2") (pinfunction "2_2") (pintype "passive"))
      (node (ref "R41") (pin "2") (pinfunction "2_2") (pintype "passive"))
      (node (ref "VT5") (pin "1") (pinfunction "G_1") (pintype "passive"))
    )
    (net (code "60") (name "Net-(VT6-G)") (class "Default")
      (node (ref "R36") (pin "2") (pinfunction "2_2") (pintype "passive"))
      (node (ref "R42") (pin "2") (pinfunction "2_2") (pintype "passive"))
      (node (ref "VT6") (pin "1") (pinfunction "G_1") (pintype "passive"))
    )
    (net (code "61") (name "VBUS") (class "Default")
      (node (ref "C10") (pin "1") (pinfunction "1_1") (pintype "passive"))
      (node (ref "C15") (pin "1") (pinfunction "1_1") (pintype "passive"))
      (node (ref "C20") (pin "2") (pinfunction "2_2") (pintype "passive"))
      (node (ref "C21") (pin "2") (pinfunction "2_2") (pintype "passive"))
      (node (ref "C22") (pin "2") (pinfunction "2_2") (pintype "passive"))
      (node (ref "DD2") (pin "3") (pinfunction "VIN_3") (pintype "passive"))
      (node (ref "R10") (pin "1") (pinfunction "1_1") (pintype "passive"))
      (node (ref "R8") (pin "2") (pinfunction "2_2") (pintype "passive"))
      (node (ref "VT1") (pin "2") (pinfunction "D_2") (pintype "passive"))
      (node (ref "VT3") (pin "2") (pinfunction "D_2") (pintype "passive"))
      (node (ref "VT5") (pin "2") (pinfunction "D_2") (pintype "passive"))
      (node (ref "X7") (pin "1") (pinfunction "1_1") (pintype "passive"))
    )
    (net (code "62") (name "VDD") (class "Default")
      (node (ref "C1") (pin "2") (pinfunction "2_2") (pintype "passive"))
      (node (ref "C19") (pin "1") (pinfunction "1_1") (pintype "passive"))
      (node (ref "C4") (pin "2") (pinfunction "2_2") (pintype "passive"))
      (node (ref "C7") (pin "2") (pinfunction "2_2") (pintype "passive"))
      (node (ref "DD1") (pin "10") (pinfunction "VDDA_10") (pintype "passive"))
      (node (ref "DD1") (pin "48") (pinfunction "VDD_48") (pintype "passive"))
      (node (ref "DD2") (pin "2") (pinfunction "VOUT_2") (pintype "passive"))
      (node (ref "DD2") (pin "4") (pinfunction "VOUT_4") (pintype "passive"))
      (node (ref "L1") (pin "1") (pinfunction "1_1") (pintype "passive"))
      (node (ref "R18") (pin "2") (pinfunction "2_2") (pintype "passive"))
      (node (ref "R20") (pin "2") (pinfunction "2_2") (pintype "passive"))
      (node (ref "R22") (pin "2") (pinfunction "2_2") (pintype "passive"))
      (node (ref "R24") (pin "2") (pinfunction "2_2") (pintype "passive"))
      (node (ref "R43") (pin "1") (pinfunction "1_1") (pintype "passive"))
      (node (ref "R5") (pin "1") (pinfunction "1_1") (pintype "passive"))
      (node (ref "R7") (pin "2") (pinfunction "2_2") (pintype "passive"))
      (node (ref "VD4") (pin "2") (pinfunction "K_2") (pintype "passive"))
      (node (ref "X1") (pin "1") (pinfunction "1_1") (pintype "passive"))
      (node (ref "X2") (pin "1") (pinfunction "VCC_1") (pintype "passive"))
    )
    (net (code "63") (name "VM") (class "Default")
      (node (ref "C2") (pin "1") (pinfunction "1_1") (pintype "passive"))
      (node (ref "C3") (pin "2") (pinfunction "2_2") (pintype "passive"))
      (node (ref "DD1") (pin "8") (pinfunction "VM_8") (pintype "passive"))
      (node (ref "R4") (pin "1") (pinfunction "1_1") (pintype "passive"))
    )
    (net (code "64") (name "VREG") (class "Default")
      (node (ref "C6") (pin "1") (pinfunction "1_1") (pintype "passive"))
      (node (ref "C8") (pin "1") (pinfunction "1_1") (pintype "passive"))
      (node (ref "DD1") (pin "6") (pinfunction "VREG12_6") (pintype "passive"))
      (node (ref "R4") (pin "2") (pinfunction "2_2") (pintype "passive"))
      (node (ref "X5") (pin "1") (pinfunction "1_1") (pintype "passive"))
    )
    (net (code "65") (name "unconnected-(DD1-OP4O-Pad3)") (class "Default")
      (node (ref "DD1") (pin "3") (pinfunction "OP4O_3") (pintype "passive"))
    )
    (net (code "66") (name "unconnected-(DD1-PA0-Pad11)") (class "Default")
      (node (ref "DD1") (pin "11") (pinfunction "PA0_11") (pintype "passive"))
    )
    (net (code "67") (name "unconnected-(DD1-PA1-Pad12)") (class "Default")
      (node (ref "DD1") (pin "12") (pinfunction "PA1_12") (pintype "passive"))
    )
    (net (code "68") (name "unconnected-(DD1-PA2-Pad13)") (class "Default")
      (node (ref "DD1") (pin "13") (pinfunction "PA2_13") (pintype "passive"))
    )
    (net (code "69") (name "unconnected-(DD1-PA6-Pad17)") (class "Default")
      (node (ref "DD1") (pin "17") (pinfunction "PA6_17") (pintype "passive"))
    )
    (net (code "70") (name "unconnected-(X3-Pad1)") (class "Default")
      (node (ref "X3") (pin "1") (pinfunction "1_1") (pintype "passive"))
    )
  )
)
